# 04_STORAGE.net
KiCad netlist of a schematic drawn in Altium Designer
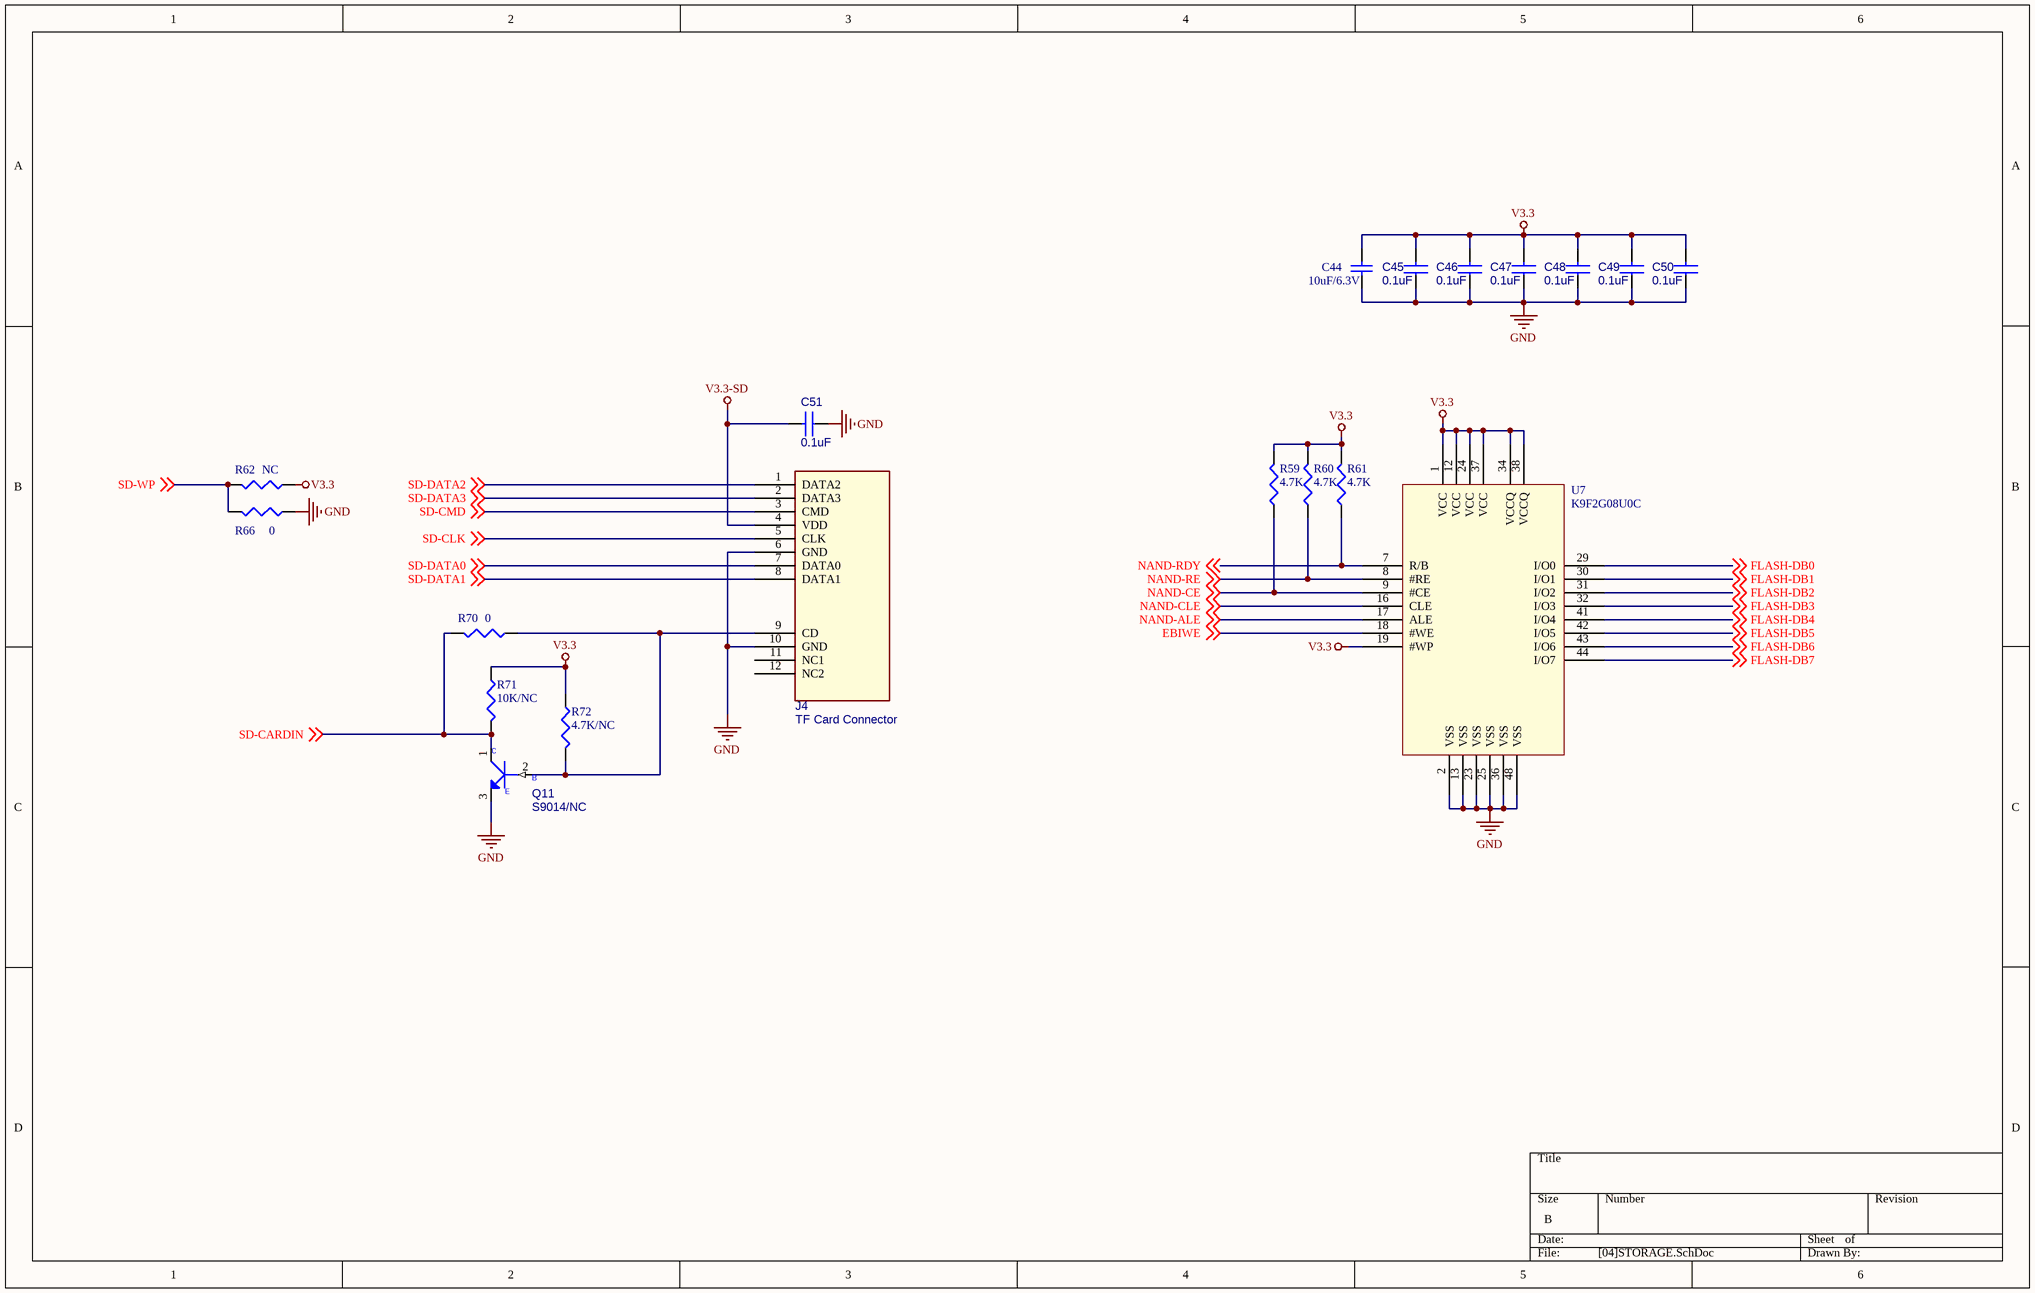
[diagram p0: [04]STORAGE.SchDoc]

(export (version "E")
  (design (tool "Eeschema 10.0.6"))
  (components
    (comp (ref "C44")
      (value "10uF/6.3V")
      (footprint "0805")
      (description "Capacitor")
      (libsource (lib "Miscellaneous Devices") (part "Cap"))
    )
    (comp (ref "C45") (value "0.1uF") (footprint "0603") (libsource (lib "*") (part "CAP NP_Dup2")))
    (comp (ref "C46") (value "0.1uF") (footprint "0603") (libsource (lib "*") (part "CAP NP_Dup2")))
    (comp (ref "C47") (value "0.1uF") (footprint "0603") (libsource (lib "*") (part "CAP NP_Dup2")))
    (comp (ref "C48") (value "0.1uF") (footprint "0603") (libsource (lib "*") (part "CAP NP_Dup2")))
    (comp (ref "C49") (value "0.1uF") (footprint "0603") (libsource (lib "*") (part "CAP NP_Dup2")))
    (comp (ref "C50") (value "0.1uF") (footprint "0603") (libsource (lib "*") (part "CAP NP_Dup2")))
    (comp (ref "C51") (value "0.1uF") (footprint "0603") (libsource (lib "*") (part "CAP NP_Dup2")))
    (comp (ref "J4")
      (value "TF Card Connector")
      (footprint "TFCARD-2")
      (description "CON;HDR,MA,9P,RA,H2.7,SMT")
      (libsource (lib "*") (part "MOLEX_1"))
    )
    (comp (ref "Q11")
      (value "S9014/NC")
      (footprint "NPN")
      (fields (field (name "PART NUMBER") "SB039040000"))
      (libsource (lib "*") (part "MMBT3904_NL_SOT23-3"))
    )
    (comp (ref "R59")
      (value "4.7K")
      (footprint "0603")
      (description "Resistor")
      (libsource (lib "Miscellaneous Devices") (part "Res3"))
    )
    (comp (ref "R60")
      (value "4.7K")
      (footprint "0603")
      (description "Resistor")
      (libsource (lib "Miscellaneous Devices") (part "Res3"))
    )
    (comp (ref "R61")
      (value "4.7K")
      (footprint "0603")
      (description "Resistor")
      (libsource (lib "Miscellaneous Devices") (part "Res3"))
    )
    (comp (ref "R62")
      (value "NC")
      (footprint "0603")
      (description "Resistor")
      (libsource (lib "Miscellaneous Devices") (part "Res3"))
    )
    (comp (ref "R66")
      (value "0")
      (footprint "0603")
      (description "Resistor")
      (libsource (lib "Miscellaneous Devices") (part "Res3"))
    )
    (comp (ref "R70")
      (value "0")
      (footprint "0603")
      (description "Resistor")
      (libsource (lib "Miscellaneous Devices") (part "Res3"))
    )
    (comp (ref "R71")
      (value "10K/NC")
      (footprint "0603")
      (description "Resistor")
      (libsource (lib "Miscellaneous Devices") (part "Res3"))
    )
    (comp (ref "R72")
      (value "4.7K/NC")
      (footprint "0603")
      (description "Resistor")
      (libsource (lib "Miscellaneous Devices") (part "Res3"))
    )
    (comp (ref "U7") (value "K9F2G08U0C") (footprint "TSOP48") (libsource (lib "Schlib") (part "K9GBG08U0A")))
  )
  (nets
    (net (code "1") (name "EBIWE") (class "Default")
      (node (ref "U7") (pin "18") (pinfunction "#WE_18") (pintype "passive"))
    )
    (net (code "2") (name "FLASH-DB0") (class "Default")
      (node (ref "U7") (pin "29") (pinfunction "I/O0_29") (pintype "passive"))
    )
    (net (code "3") (name "FLASH-DB1") (class "Default")
      (node (ref "U7") (pin "30") (pinfunction "I/O1_30") (pintype "passive"))
    )
    (net (code "4") (name "FLASH-DB2") (class "Default")
      (node (ref "U7") (pin "31") (pinfunction "I/O2_31") (pintype "passive"))
    )
    (net (code "5") (name "FLASH-DB3") (class "Default")
      (node (ref "U7") (pin "32") (pinfunction "I/O3_32") (pintype "passive"))
    )
    (net (code "6") (name "FLASH-DB4") (class "Default")
      (node (ref "U7") (pin "41") (pinfunction "I/O4_41") (pintype "passive"))
    )
    (net (code "7") (name "FLASH-DB5") (class "Default")
      (node (ref "U7") (pin "42") (pinfunction "I/O5_42") (pintype "passive"))
    )
    (net (code "8") (name "FLASH-DB6") (class "Default")
      (node (ref "U7") (pin "43") (pinfunction "I/O6_43") (pintype "passive"))
    )
    (net (code "9") (name "FLASH-DB7") (class "Default")
      (node (ref "U7") (pin "44") (pinfunction "I/O7_44") (pintype "passive"))
    )
    (net (code "10") (name "GND") (class "Default")
      (node (ref "C44") (pin "1") (pinfunction "1_1") (pintype "passive"))
      (node (ref "C45") (pin "1") (pinfunction "1_1") (pintype "passive"))
      (node (ref "C46") (pin "1") (pinfunction "1_1") (pintype "passive"))
      (node (ref "C47") (pin "1") (pinfunction "1_1") (pintype "passive"))
      (node (ref "C48") (pin "1") (pinfunction "1_1") (pintype "passive"))
      (node (ref "C49") (pin "1") (pinfunction "1_1") (pintype "passive"))
      (node (ref "C50") (pin "1") (pinfunction "1_1") (pintype "passive"))
      (node (ref "C51") (pin "1") (pinfunction "1_1") (pintype "passive"))
      (node (ref "J4") (pin "10") (pinfunction "GND_10") (pintype "power_in"))
      (node (ref "J4") (pin "6") (pinfunction "GND_6") (pintype "power_in"))
      (node (ref "Q11") (pin "3") (pinfunction "EMITTER_3") (pintype "passive"))
      (node (ref "R66") (pin "1") (pinfunction "1_1") (pintype "passive"))
      (node (ref "U7") (pin "13") (pinfunction "VSS_13") (pintype "passive"))
      (node (ref "U7") (pin "2") (pinfunction "VSS_2") (pintype "passive"))
      (node (ref "U7") (pin "23") (pinfunction "VSS_23") (pintype "passive"))
      (node (ref "U7") (pin "25") (pinfunction "VSS_25") (pintype "passive"))
      (node (ref "U7") (pin "36") (pinfunction "VSS_36") (pintype "passive"))
      (node (ref "U7") (pin "48") (pinfunction "VSS_48") (pintype "passive"))
    )
    (net (code "11") (name "NAND-ALE") (class "Default")
      (node (ref "U7") (pin "17") (pinfunction "ALE_17") (pintype "passive"))
    )
    (net (code "12") (name "NAND-CE") (class "Default")
      (node (ref "R59") (pin "1") (pinfunction "1_1") (pintype "passive"))
      (node (ref "U7") (pin "9") (pinfunction "#CE_9") (pintype "passive"))
    )
    (net (code "13") (name "NAND-CLE") (class "Default")
      (node (ref "U7") (pin "16") (pinfunction "CLE_16") (pintype "passive"))
    )
    (net (code "14") (name "NAND-RDY") (class "Default")
      (node (ref "R61") (pin "1") (pinfunction "1_1") (pintype "passive"))
      (node (ref "U7") (pin "7") (pinfunction "R/B_7") (pintype "passive"))
    )
    (net (code "15") (name "NAND-RE") (class "Default")
      (node (ref "R60") (pin "1") (pinfunction "1_1") (pintype "passive"))
      (node (ref "U7") (pin "8") (pinfunction "#RE_8") (pintype "passive"))
    )
    (net (code "16") (name "Net-(J4-CD)") (class "Default")
      (node (ref "J4") (pin "9") (pinfunction "CD_9") (pintype "passive"))
      (node (ref "Q11") (pin "2") (pinfunction "BASE_2") (pintype "input"))
      (node (ref "R70") (pin "1") (pinfunction "1_1") (pintype "passive"))
      (node (ref "R72") (pin "2") (pinfunction "2_2") (pintype "passive"))
    )
    (net (code "17") (name "SD-CARDIN") (class "Default")
      (node (ref "Q11") (pin "1") (pinfunction "COLLECTOR_1") (pintype "passive"))
      (node (ref "R70") (pin "2") (pinfunction "2_2") (pintype "passive"))
      (node (ref "R71") (pin "2") (pinfunction "2_2") (pintype "passive"))
    )
    (net (code "18") (name "SD-CLK") (class "Default")
      (node (ref "J4") (pin "5") (pinfunction "CLK_5") (pintype "passive"))
    )
    (net (code "19") (name "SD-CMD") (class "Default")
      (node (ref "J4") (pin "3") (pinfunction "CMD_3") (pintype "passive"))
    )
    (net (code "20") (name "SD-DATA0") (class "Default")
      (node (ref "J4") (pin "7") (pinfunction "DATA0_7") (pintype "passive"))
    )
    (net (code "21") (name "SD-DATA1") (class "Default")
      (node (ref "J4") (pin "8") (pinfunction "DATA1_8") (pintype "passive"))
    )
    (net (code "22") (name "SD-DATA2") (class "Default")
      (node (ref "J4") (pin "1") (pinfunction "DATA2_1") (pintype "passive"))
    )
    (net (code "23") (name "SD-DATA3") (class "Default")
      (node (ref "J4") (pin "2") (pinfunction "DATA3_2") (pintype "passive"))
    )
    (net (code "24") (name "SD-WP") (class "Default")
      (node (ref "R62") (pin "2") (pinfunction "2_2") (pintype "passive"))
      (node (ref "R66") (pin "2") (pinfunction "2_2") (pintype "passive"))
    )
    (net (code "25") (name "V3.3") (class "Default")
      (node (ref "C44") (pin "2") (pinfunction "2_2") (pintype "passive"))
      (node (ref "C45") (pin "2") (pinfunction "2_2") (pintype "passive"))
      (node (ref "C46") (pin "2") (pinfunction "2_2") (pintype "passive"))
      (node (ref "C47") (pin "2") (pinfunction "2_2") (pintype "passive"))
      (node (ref "C48") (pin "2") (pinfunction "2_2") (pintype "passive"))
      (node (ref "C49") (pin "2") (pinfunction "2_2") (pintype "passive"))
      (node (ref "C50") (pin "2") (pinfunction "2_2") (pintype "passive"))
      (node (ref "R59") (pin "2") (pinfunction "2_2") (pintype "passive"))
      (node (ref "R60") (pin "2") (pinfunction "2_2") (pintype "passive"))
      (node (ref "R61") (pin "2") (pinfunction "2_2") (pintype "passive"))
      (node (ref "R62") (pin "1") (pinfunction "1_1") (pintype "passive"))
      (node (ref "R71") (pin "1") (pinfunction "1_1") (pintype "passive"))
      (node (ref "R72") (pin "1") (pinfunction "1_1") (pintype "passive"))
      (node (ref "U7") (pin "1") (pinfunction "VCC_1") (pintype "passive"))
      (node (ref "U7") (pin "12") (pinfunction "VCC_12") (pintype "passive"))
      (node (ref "U7") (pin "19") (pinfunction "#WP_19") (pintype "passive"))
      (node (ref "U7") (pin "24") (pinfunction "VCC_24") (pintype "passive"))
      (node (ref "U7") (pin "34") (pinfunction "VCCQ_34") (pintype "passive"))
      (node (ref "U7") (pin "37") (pinfunction "VCC_37") (pintype "passive"))
      (node (ref "U7") (pin "38") (pinfunction "VCCQ_38") (pintype "passive"))
    )
    (net (code "26") (name "V3.3-SD") (class "Default")
      (node (ref "C51") (pin "2") (pinfunction "2_2") (pintype "passive"))
      (node (ref "J4") (pin "4") (pinfunction "VDD_4") (pintype "passive"))
    )
    (net (code "27") (name "unconnected-(J4-NC1-Pad11)") (class "Default")
      (node (ref "J4") (pin "11") (pinfunction "NC1_11") (pintype "passive"))
    )
    (net (code "28") (name "unconnected-(J4-NC2-Pad12)") (class "Default")
      (node (ref "J4") (pin "12") (pinfunction "NC2_12") (pintype "passive"))
    )
  )
)
